# ultrasonic_tx.net
KiCad netlist of a schematic drawn in Altium Designer
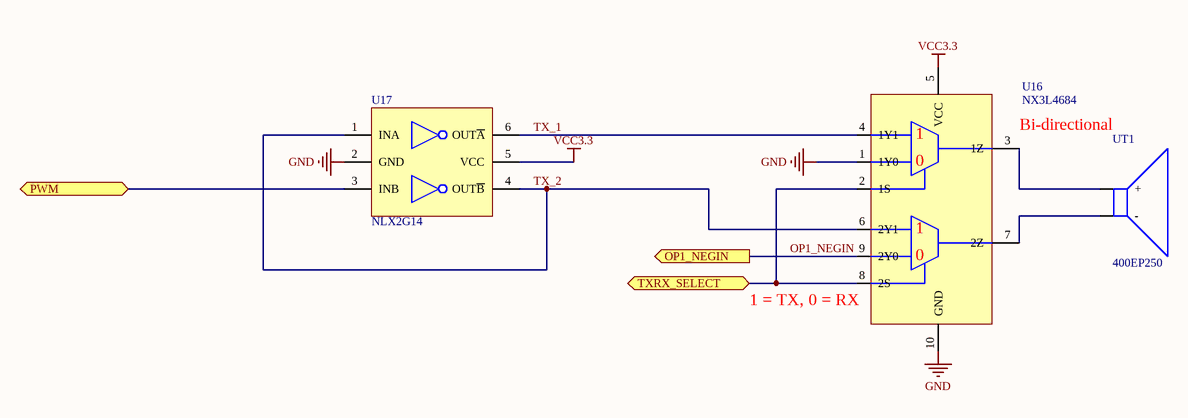
[diagram p0: ultrasonic_tx.SchDoc]

(export (version "E")
  (design (tool "Eeschema 10.0.6"))
  (components
    (comp (ref "U16")
      (value "NX3L4684")
      (footprint "QFN50P155X200X13-10N")
      (description "IC ANALOG SWITCH SPDT 10XQFN")
      (libsource (lib "opo") (part "NX3L4684"))
    )
    (comp (ref "U17")
      (value "NLX2G14")
      (footprint "ULLGA6")
      (description "Dual Schmitt-Trigger  Inverter")
      (libsource (lib "opo") (part "NLX2G14"))
    )
    (comp (ref "UT1")
      (value "400EP250")
      (footprint "Transducer recepticle")
      (description "Air Ultrasounic Ceramic Transducers")
      (libsource (lib "opo") (part "Tranducer"))
    )
  )
  (nets
    (net (code "1") (name "/OP1_NEGIN") (class "Default")
      (node (ref "U16") (pin "9") (pinfunction "2Y0_9") (pintype "passive"))
    )
    (net (code "2") (name "/PWM") (class "Default")
      (node (ref "U17") (pin "3") (pinfunction "INB_3") (pintype "passive"))
    )
    (net (code "3") (name "/TXRX_SELECT") (class "Default")
      (node (ref "U16") (pin "2") (pinfunction "1S_2") (pintype "passive"))
      (node (ref "U16") (pin "8") (pinfunction "2S_8") (pintype "passive"))
    )
    (net (code "4") (name "/TX_1") (class "Default")
      (node (ref "U16") (pin "4") (pinfunction "1Y1_4") (pintype "passive"))
      (node (ref "U17") (pin "6") (pinfunction "OUT~{A}_6") (pintype "passive"))
    )
    (net (code "5") (name "/TX_2") (class "Default")
      (node (ref "U16") (pin "6") (pinfunction "2Y1_6") (pintype "passive"))
      (node (ref "U17") (pin "1") (pinfunction "INA_1") (pintype "passive"))
      (node (ref "U17") (pin "4") (pinfunction "OUT~{B}_4") (pintype "passive"))
    )
    (net (code "6") (name "GND") (class "Default")
      (node (ref "U16") (pin "1") (pinfunction "1Y0_1") (pintype "passive"))
      (node (ref "U16") (pin "10") (pinfunction "GND_10") (pintype "passive"))
      (node (ref "U17") (pin "2") (pinfunction "GND_2") (pintype "passive"))
    )
    (net (code "7") (name "Net-(U16-1Z)") (class "Default")
      (node (ref "U16") (pin "3") (pinfunction "1Z_3") (pintype "passive"))
      (node (ref "UT1") (pin "2") (pinfunction "+_2") (pintype "passive"))
    )
    (net (code "8") (name "Net-(U16-2Z)") (class "Default")
      (node (ref "U16") (pin "7") (pinfunction "2Z_7") (pintype "passive"))
      (node (ref "UT1") (pin "1") (pinfunction "-_1") (pintype "passive"))
    )
    (net (code "9") (name "VCC3.3") (class "Default")
      (node (ref "U16") (pin "5") (pinfunction "VCC_5") (pintype "passive"))
      (node (ref "U17") (pin "5") (pinfunction "VCC_5") (pintype "passive"))
    )
  )
)
